# schem.net
KiCad netlist of a schematic drawn in EAGLE
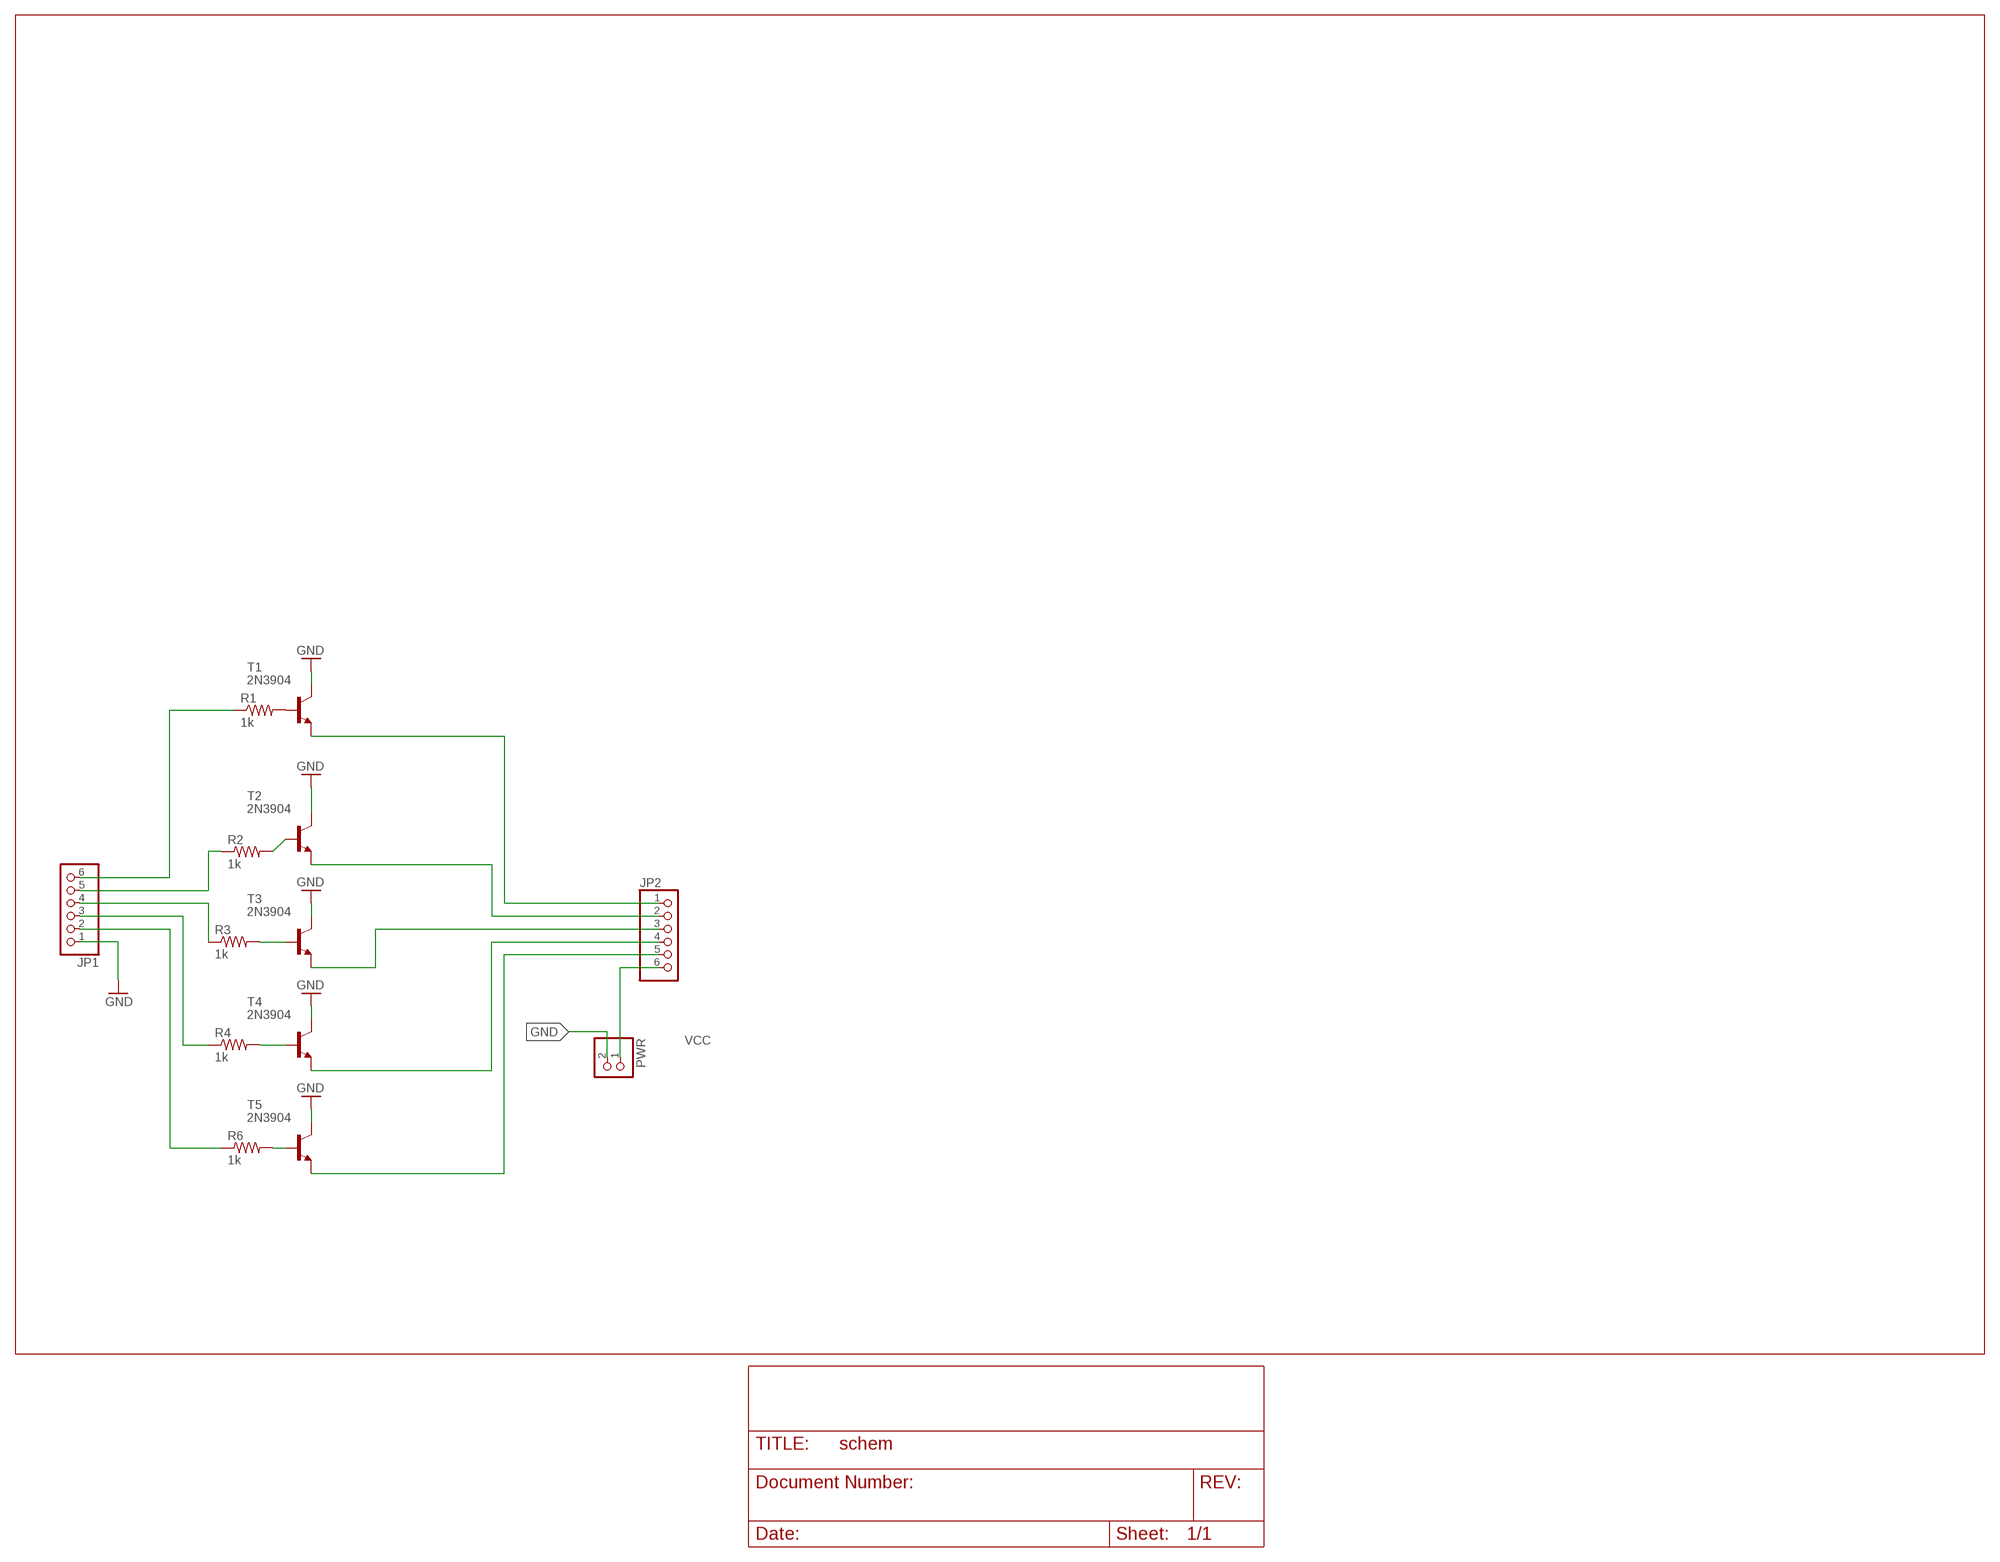
[diagram p0: schematic, sheet 1]

(export (version "E")
  (design (tool "Eeschema 10.0.6"))
  (components
    (comp (ref "JP1")
      (value "PINHD-1X6")
      (footprint "eagle-import:1X06")
      (libsource (lib "eagle-import") (part "PINHD-1X6"))
    )
    (comp (ref "JP2")
      (value "PINHD-1X6")
      (footprint "eagle-import:1X06")
      (fields (field (name "SPICEPREFIX") "X"))
      (libsource (lib "eagle-import") (part "PINHD-1X6"))
    )
    (comp (ref "PWR")
      (value "PINHD-1X2")
      (footprint "eagle-import:1X02")
      (libsource (lib "eagle-import") (part "PINHD-1X2"))
    )
    (comp (ref "R1")
      (value "1k")
      (footprint "eagle-import:0207_5V")
      (libsource (lib "eagle-import") (part "R-US_0207/5V"))
    )
    (comp (ref "R2")
      (value "1k")
      (footprint "eagle-import:0207_5V")
      (libsource (lib "eagle-import") (part "R-US_0207/5V"))
    )
    (comp (ref "R3")
      (value "1k")
      (footprint "eagle-import:0207_5V")
      (libsource (lib "eagle-import") (part "R-US_0207/5V"))
    )
    (comp (ref "R4")
      (value "1k")
      (footprint "eagle-import:0207_5V")
      (libsource (lib "eagle-import") (part "R-US_0207/5V"))
    )
    (comp (ref "R6")
      (value "1k")
      (footprint "eagle-import:0207_5V")
      (libsource (lib "eagle-import") (part "R-US_0207/5V"))
    )
    (comp (ref "T1")
      (value "2N3904")
      (footprint "eagle-import:TO92")
      (libsource (lib "eagle-import") (part "2N3904"))
    )
    (comp (ref "T2")
      (value "2N3904")
      (footprint "eagle-import:TO92")
      (libsource (lib "eagle-import") (part "2N3904"))
    )
    (comp (ref "T3")
      (value "2N3904")
      (footprint "eagle-import:TO92")
      (libsource (lib "eagle-import") (part "2N3904"))
    )
    (comp (ref "T4")
      (value "2N3904")
      (footprint "eagle-import:TO92")
      (libsource (lib "eagle-import") (part "2N3904"))
    )
    (comp (ref "T5")
      (value "2N3904")
      (footprint "eagle-import:TO92")
      (libsource (lib "eagle-import") (part "2N3904"))
    )
  )
  (nets
    (net (code "1") (name "/VCC") (class "Default")
      (node (ref "JP2") (pin "6") (pinfunction "6_6") (pintype "passive"))
      (node (ref "PWR") (pin "1") (pinfunction "1_1") (pintype "passive"))
    )
    (net (code "2") (name "GND") (class "Default")
      (node (ref "JP1") (pin "1") (pinfunction "1_1") (pintype "passive"))
      (node (ref "PWR") (pin "2") (pinfunction "2_2") (pintype "passive"))
      (node (ref "T1") (pin "1") (pinfunction "C_1") (pintype "passive"))
      (node (ref "T2") (pin "1") (pinfunction "C_1") (pintype "passive"))
      (node (ref "T3") (pin "1") (pinfunction "C_1") (pintype "passive"))
      (node (ref "T4") (pin "1") (pinfunction "C_1") (pintype "passive"))
      (node (ref "T5") (pin "1") (pinfunction "C_1") (pintype "passive"))
    )
    (net (code "3") (name "Net-(JP1-Pad2)") (class "Default")
      (node (ref "JP1") (pin "2") (pinfunction "2_2") (pintype "passive"))
      (node (ref "R6") (pin "1") (pinfunction "1_1") (pintype "passive"))
    )
    (net (code "4") (name "Net-(JP1-Pad3)") (class "Default")
      (node (ref "JP1") (pin "3") (pinfunction "3_3") (pintype "passive"))
      (node (ref "R4") (pin "1") (pinfunction "1_1") (pintype "passive"))
    )
    (net (code "5") (name "Net-(JP1-Pad4)") (class "Default")
      (node (ref "JP1") (pin "4") (pinfunction "4_4") (pintype "passive"))
      (node (ref "R3") (pin "1") (pinfunction "1_1") (pintype "passive"))
    )
    (net (code "6") (name "Net-(JP1-Pad5)") (class "Default")
      (node (ref "JP1") (pin "5") (pinfunction "5_5") (pintype "passive"))
      (node (ref "R2") (pin "1") (pinfunction "1_1") (pintype "passive"))
    )
    (net (code "7") (name "Net-(JP1-Pad6)") (class "Default")
      (node (ref "JP1") (pin "6") (pinfunction "6_6") (pintype "passive"))
      (node (ref "R1") (pin "1") (pinfunction "1_1") (pintype "passive"))
    )
    (net (code "8") (name "Net-(T1-B)") (class "Default")
      (node (ref "R1") (pin "2") (pinfunction "2_2") (pintype "passive"))
      (node (ref "T1") (pin "2") (pinfunction "B_2") (pintype "passive"))
    )
    (net (code "9") (name "Net-(T1-E)") (class "Default")
      (node (ref "JP2") (pin "1") (pinfunction "1_1") (pintype "passive"))
      (node (ref "T1") (pin "3") (pinfunction "E_3") (pintype "passive"))
    )
    (net (code "10") (name "Net-(T2-B)") (class "Default")
      (node (ref "R2") (pin "2") (pinfunction "2_2") (pintype "passive"))
      (node (ref "T2") (pin "2") (pinfunction "B_2") (pintype "passive"))
    )
    (net (code "11") (name "Net-(T2-E)") (class "Default")
      (node (ref "JP2") (pin "2") (pinfunction "2_2") (pintype "passive"))
      (node (ref "T2") (pin "3") (pinfunction "E_3") (pintype "passive"))
    )
    (net (code "12") (name "Net-(T3-B)") (class "Default")
      (node (ref "R3") (pin "2") (pinfunction "2_2") (pintype "passive"))
      (node (ref "T3") (pin "2") (pinfunction "B_2") (pintype "passive"))
    )
    (net (code "13") (name "Net-(T3-E)") (class "Default")
      (node (ref "JP2") (pin "3") (pinfunction "3_3") (pintype "passive"))
      (node (ref "T3") (pin "3") (pinfunction "E_3") (pintype "passive"))
    )
    (net (code "14") (name "Net-(T4-B)") (class "Default")
      (node (ref "R4") (pin "2") (pinfunction "2_2") (pintype "passive"))
      (node (ref "T4") (pin "2") (pinfunction "B_2") (pintype "passive"))
    )
    (net (code "15") (name "Net-(T4-E)") (class "Default")
      (node (ref "JP2") (pin "4") (pinfunction "4_4") (pintype "passive"))
      (node (ref "T4") (pin "3") (pinfunction "E_3") (pintype "passive"))
    )
    (net (code "16") (name "Net-(T5-B)") (class "Default")
      (node (ref "R6") (pin "2") (pinfunction "2_2") (pintype "passive"))
      (node (ref "T5") (pin "2") (pinfunction "B_2") (pintype "passive"))
    )
    (net (code "17") (name "Net-(T5-E)") (class "Default")
      (node (ref "JP2") (pin "5") (pinfunction "5_5") (pintype "passive"))
      (node (ref "T5") (pin "3") (pinfunction "E_3") (pintype "passive"))
    )
  )
)
